# ECG_Regulator.net
KiCad netlist of a schematic drawn in Altium Designer
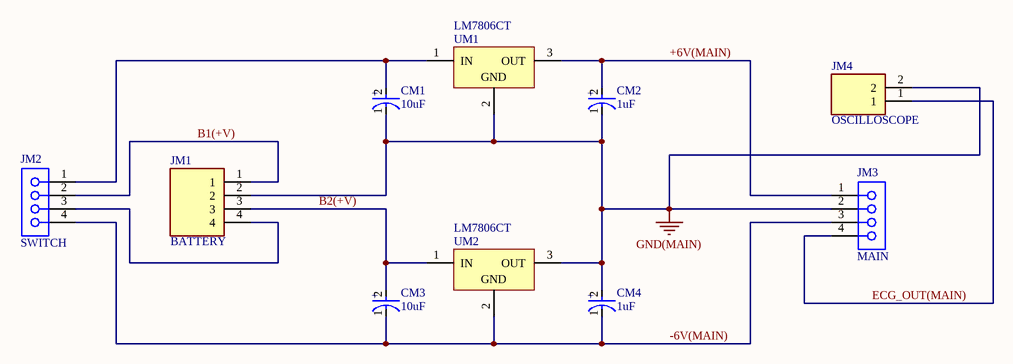
[diagram p0: ECG_Regulator.SchDoc]

(export (version "E")
  (design (tool "Eeschema 10.0.6"))
  (components
    (comp (ref "CM1")
      (value "10uF")
      (footprint "FP-RAD-TH-D_6_3_0_5-L_11-MFG")
      (description "Cap Aluminum Lytic 100uF 25V 20% (6.3 X 11.2mm) Radial 2.5mm 130mA 1000h 105°C Ammo Pack")
      (libsource (lib "University of Moratuwa") (part "203bc49f2ac43e59fd269a8c329ed05"))
    )
    (comp (ref "CM2")
      (value "1uF")
      (footprint "FP-RAD-TH-D_6_3_0_5-L_11-MFG")
      (description "Cap Aluminum Lytic 100uF 25V 20% (6.3 X 11.2mm) Radial 2.5mm 130mA 1000h 105°C Ammo Pack")
      (libsource (lib "University of Moratuwa") (part "203bc49f2ac43e59fd269a8c329ed05"))
    )
    (comp (ref "CM3")
      (value "10uF")
      (footprint "FP-RAD-TH-D_6_3_0_5-L_11-MFG")
      (description "Cap Aluminum Lytic 100uF 25V 20% (6.3 X 11.2mm) Radial 2.5mm 130mA 1000h 105°C Ammo Pack")
      (libsource (lib "University of Moratuwa") (part "203bc49f2ac43e59fd269a8c329ed05"))
    )
    (comp (ref "CM4")
      (value "1uF")
      (footprint "FP-RAD-TH-D_6_3_0_5-L_11-MFG")
      (description "Cap Aluminum Lytic 100uF 25V 20% (6.3 X 11.2mm) Radial 2.5mm 130mA 1000h 105°C Ammo Pack")
      (libsource (lib "University of Moratuwa") (part "203bc49f2ac43e59fd269a8c329ed05"))
    )
    (comp (ref "JM1")
      (value "BATTERY")
      (footprint "CUI_TB001-500-04BE")
      (fields (field (name "MP") "TB001-500-04BE") (field (name "MF") "{'manufacturer': u'CUI Devices'}"))
      (libsource (lib "SnapEDA_Library") (part "TB001-500-04BE"))
    )
    (comp (ref "JM2")
      (value "SWITCH")
      (footprint "SMTC-SLW-104-01-X-S")
      (fields (field (name "MANUFACTURER") "Samtec") (field (name "PARTNUMBER") "SLW-104-01-G-S"))
      (libsource (lib "Altium Content Vault") (part "SMTC-SLW-104-01-X-S"))
    )
    (comp (ref "JM3")
      (value "MAIN")
      (footprint "SMTC-SLW-104-01-X-S")
      (fields (field (name "MANUFACTURER") "Samtec") (field (name "PARTNUMBER") "SLW-104-01-G-S"))
      (libsource (lib "Altium Content Vault") (part "SMTC-SLW-104-01-X-S"))
    )
    (comp (ref "JM4")
      (value "OSCILLOSCOPE")
      (footprint "CUI_TB001-500-02BE")
      (fields (field (name "MP") "TB001-500-02BE") (field (name "MF") "{'manufacturer': u'CUI Devices'}"))
      (libsource (lib "SnapEDA_Library") (part "TB001-500-02BE"))
    )
    (comp (ref "UM1")
      (value "LM7806CT")
      (footprint "TO220")
      (description "Positive Voltage Regulator, 6V, 3-Pin TO-220")
      (libsource (lib "Altium Content Vault") (part "PM-REG-L4940-SIL3"))
    )
    (comp (ref "UM2")
      (value "LM7806CT")
      (footprint "TO220")
      (description "Positive Voltage Regulator, 6V, 3-Pin TO-220")
      (libsource (lib "Altium Content Vault") (part "PM-REG-L4940-SIL3"))
    )
  )
  (nets
    (net (code "1") (name "/+6V(MAIN)") (class "Default")
      (node (ref "CM2") (pin "2") (pinfunction "A_2") (pintype "passive"))
      (node (ref "JM3") (pin "1") (pinfunction "1_1") (pintype "passive"))
      (node (ref "UM1") (pin "3") (pinfunction "OUT_3") (pintype "power_in"))
    )
    (net (code "2") (name "/-6V(MAIN)") (class "Default")
      (node (ref "CM3") (pin "1") (pinfunction "C_1") (pintype "passive"))
      (node (ref "CM4") (pin "1") (pinfunction "C_1") (pintype "passive"))
      (node (ref "JM2") (pin "4") (pinfunction "4_4") (pintype "passive"))
      (node (ref "JM3") (pin "3") (pinfunction "3_3") (pintype "passive"))
      (node (ref "UM2") (pin "2") (pinfunction "GND_2") (pintype "power_in"))
    )
    (net (code "3") (name "/B1(+V)") (class "Default")
      (node (ref "JM1") (pin "1") (pinfunction "1_1") (pintype "passive"))
      (node (ref "JM2") (pin "2") (pinfunction "2_2") (pintype "passive"))
    )
    (net (code "4") (name "/B2(+V)") (class "Default")
      (node (ref "CM3") (pin "2") (pinfunction "A_2") (pintype "passive"))
      (node (ref "JM1") (pin "3") (pinfunction "3_3") (pintype "passive"))
      (node (ref "UM2") (pin "1") (pinfunction "IN_1") (pintype "power_in"))
    )
    (net (code "5") (name "/ECG_OUT(MAIN)") (class "Default")
      (node (ref "JM3") (pin "4") (pinfunction "4_4") (pintype "passive"))
      (node (ref "JM4") (pin "1") (pinfunction "1_1") (pintype "passive"))
    )
    (net (code "6") (name "GND(MAIN)") (class "Default")
      (node (ref "CM1") (pin "1") (pinfunction "C_1") (pintype "passive"))
      (node (ref "CM2") (pin "1") (pinfunction "C_1") (pintype "passive"))
      (node (ref "CM4") (pin "2") (pinfunction "A_2") (pintype "passive"))
      (node (ref "JM1") (pin "2") (pinfunction "2_2") (pintype "passive"))
      (node (ref "JM3") (pin "2") (pinfunction "2_2") (pintype "passive"))
      (node (ref "JM4") (pin "2") (pinfunction "2_2") (pintype "passive"))
      (node (ref "UM1") (pin "2") (pinfunction "GND_2") (pintype "power_in"))
      (node (ref "UM2") (pin "3") (pinfunction "OUT_3") (pintype "power_in"))
    )
    (net (code "7") (name "Net-(CM1-A)") (class "Default")
      (node (ref "CM1") (pin "2") (pinfunction "A_2") (pintype "passive"))
      (node (ref "JM2") (pin "1") (pinfunction "1_1") (pintype "passive"))
      (node (ref "UM1") (pin "1") (pinfunction "IN_1") (pintype "power_in"))
    )
    (net (code "8") (name "Net-(JM1-Pad4)") (class "Default")
      (node (ref "JM1") (pin "4") (pinfunction "4_4") (pintype "passive"))
      (node (ref "JM2") (pin "3") (pinfunction "3_3") (pintype "passive"))
    )
  )
)
